# 1_0020-03_FFT2G_-_Top.net
KiCad netlist of a schematic drawn in Altium Designer
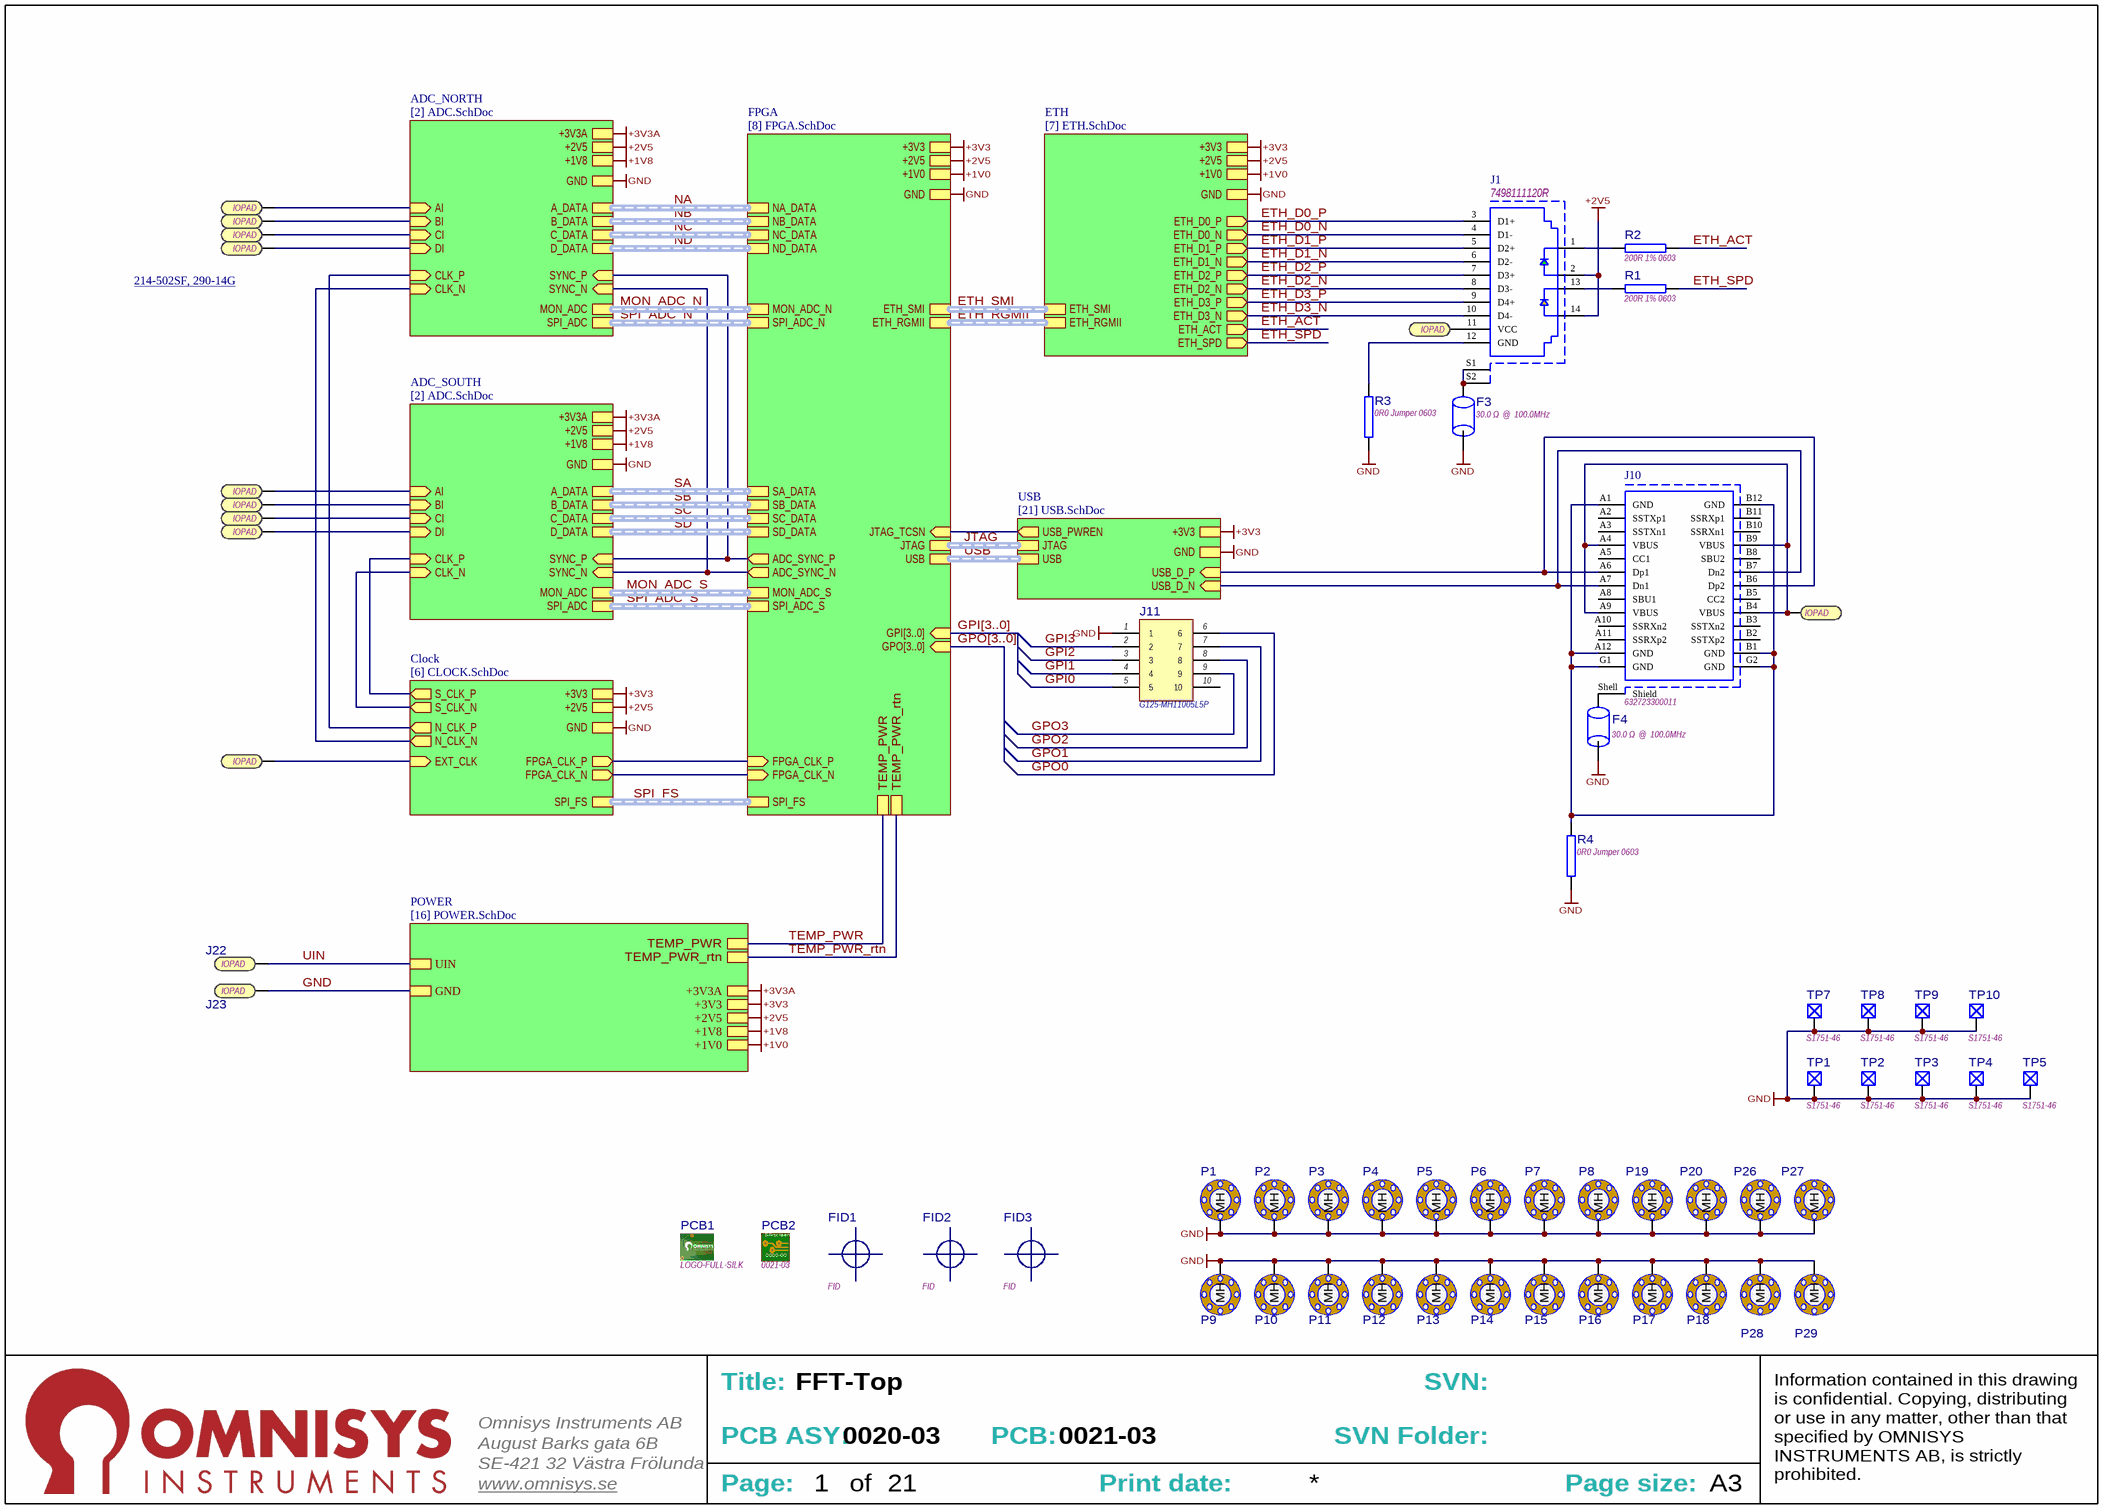
[diagram p0: [1] 0020-03_FFT2G - Top.SchDoc]

(export (version "E")
  (design (tool "Eeschema 10.0.6"))
  (components
    (comp (ref "F3")
      (value "30.0 Ω  @  100.0MHz")
      (footprint "INDC2012X11N")
      (description "Ferrite bead, Würth Elektronik WE-CBF 2012 (0805), 74279206 ,  30.0 Ω  @  100.0MHz")
      (fields (field (name "PARTNUMBER") "74279206"))
      (libsource (lib "Omnisys Vault") (part "BEAD-2PIN"))
    )
    (comp (ref "F4")
      (value "30.0 Ω  @  100.0MHz")
      (footprint "INDC2012X11N")
      (description "Ferrite bead, Würth Elektronik WE-CBF 2012 (0805), 74279206 ,  30.0 Ω  @  100.0MHz")
      (fields (field (name "PARTNUMBER") "74279206"))
      (libsource (lib "Omnisys Vault") (part "BEAD-2PIN"))
    )
    (comp (ref "FID1")
      (value "FID")
      (footprint "FID")
      (description "Pick and place fiducial")
      (libsource (lib "Omnisys Vault") (part "FID"))
    )
    (comp (ref "FID2")
      (value "FID")
      (footprint "FID")
      (description "Pick and place fiducial")
      (libsource (lib "Omnisys Vault") (part "FID"))
    )
    (comp (ref "FID3")
      (value "FID")
      (footprint "FID")
      (description "Pick and place fiducial")
      (libsource (lib "Omnisys Vault") (part "FID"))
    )
    (comp (ref "J1")
      (value "7498111120R")
      (footprint "7498111120R-Footprint-1")
      (description "CONN MAGJACK 1PORT 1000 BASE-T")
      (fields (field (name "PARTNUMBER") "7498111120AR"))
      (libsource (lib "Omnisys Vault") (part "7498111120R"))
    )
    (comp (ref "J2")
      (value "IOPAD")
      (footprint "SMT_IO_PAD_0.5x0.5MM")
      (description "Square IO pad 0.5x0.5mm used for test points and flying leads.")
      (libsource (lib "Omnisys Vault") (part "SMT_IOPAD"))
    )
    (comp (ref "J3")
      (value "IOPAD")
      (footprint "SMT_IO_PAD_0.5x0.5MM")
      (description "Square IO pad 0.5x0.5mm used for test points and flying leads.")
      (libsource (lib "Omnisys Vault") (part "SMT_IOPAD"))
    )
    (comp (ref "J4")
      (value "IOPAD")
      (footprint "SMT_IO_PAD_0.5x0.5MM")
      (description "Square IO pad 0.5x0.5mm used for test points and flying leads.")
      (libsource (lib "Omnisys Vault") (part "SMT_IOPAD"))
    )
    (comp (ref "J5")
      (value "IOPAD")
      (footprint "SMT_IO_PAD_0.5x0.5MM")
      (description "Square IO pad 0.5x0.5mm used for test points and flying leads.")
      (libsource (lib "Omnisys Vault") (part "SMT_IOPAD"))
    )
    (comp (ref "J6")
      (value "IOPAD")
      (footprint "SMT_IO_PAD_0.5x0.5MM")
      (description "Square IO pad 0.5x0.5mm used for test points and flying leads.")
      (libsource (lib "Omnisys Vault") (part "SMT_IOPAD"))
    )
    (comp (ref "J7")
      (value "IOPAD")
      (footprint "SMT_IO_PAD_0.5x0.5MM")
      (description "Square IO pad 0.5x0.5mm used for test points and flying leads.")
      (libsource (lib "Omnisys Vault") (part "SMT_IOPAD"))
    )
    (comp (ref "J8")
      (value "IOPAD")
      (footprint "SMT_IO_PAD_0.5x0.5MM")
      (description "Square IO pad 0.5x0.5mm used for test points and flying leads.")
      (libsource (lib "Omnisys Vault") (part "SMT_IOPAD"))
    )
    (comp (ref "J9")
      (value "IOPAD")
      (footprint "SMT_IO_PAD_0.5x0.5MM")
      (description "Square IO pad 0.5x0.5mm used for test points and flying leads.")
      (libsource (lib "Omnisys Vault") (part "SMT_IOPAD"))
    )
    (comp (ref "J10")
      (value "632723300011")
      (footprint "632723300011")
      (description "USB 3.1 Type C Receptacle WR-COM, Horizontal, SMT / THT")
      (fields (field (name "MANUFACTURER") "Wurth Elektronik") (field (name "PUBLISHER") "WurthElektronik"))
      (libsource (lib "Altium Content Vault") (part "WE-632723X00011"))
    )
    (comp (ref "J11")
      (value "G125-MH11005L5P")
      (footprint "G125-MH11005L5P-Footprint-1")
      (description "CONN HDR 1.25MM R/A PCB 10POS")
      (libsource (lib "Omnisys Vault") (part "CON-2ROW-10PIN-COL"))
    )
    (comp (ref "J15")
      (value "IOPAD")
      (footprint "SMT_IO_PAD_0.5x0.5MM")
      (description "Square IO pad 0.5x0.5mm used for test points and flying leads.")
      (libsource (lib "Omnisys Vault") (part "SMT_IOPAD"))
    )
    (comp (ref "J17")
      (value "IOPAD")
      (footprint "SMT_IO_PAD_2x1MM")
      (description "IO pad used for test points and flying leads.")
      (libsource (lib "Omnisys Vault") (part "SMT_IOPAD"))
    )
    (comp (ref "J18")
      (value "IOPAD")
      (footprint "SMT_IO_PAD_2x1MM")
      (description "IO pad used for test points and flying leads.")
      (libsource (lib "Omnisys Vault") (part "SMT_IOPAD"))
    )
    (comp (ref "J22")
      (value "IOPAD")
      (footprint "SMT_IO_PAD_4x2MM")
      (description "IO pad used for test points and flying leads.")
      (libsource (lib "Omnisys Vault") (part "SMT_IOPAD"))
    )
    (comp (ref "J23")
      (value "IOPAD")
      (footprint "SMT_IO_PAD_4x2MM")
      (description "IO pad used for test points and flying leads.")
      (libsource (lib "Omnisys Vault") (part "SMT_IOPAD"))
    )
    (comp (ref "P1")
      (value "M2.5-6.3mm pad")
      (footprint "MH6.3-2_7MM")
      (description "Mounting hole, M2.5-6.3mm pad")
      (libsource (lib "Omnisys Vault") (part "MH"))
    )
    (comp (ref "P2")
      (value "M2.5-6.3mm pad")
      (footprint "MH6.3-2_7MM")
      (description "Mounting hole, M2.5-6.3mm pad")
      (libsource (lib "Omnisys Vault") (part "MH"))
    )
    (comp (ref "P3")
      (value "M2.5-6.3mm pad")
      (footprint "MH6.3-2_7MM")
      (description "Mounting hole, M2.5-6.3mm pad")
      (libsource (lib "Omnisys Vault") (part "MH"))
    )
    (comp (ref "P4")
      (value "M2.5-6.3mm pad")
      (footprint "MH6.3-2_7MM")
      (description "Mounting hole, M2.5-6.3mm pad")
      (libsource (lib "Omnisys Vault") (part "MH"))
    )
    (comp (ref "P5")
      (value "M2.5-6.3mm pad")
      (footprint "MH6.3-2_7MM")
      (description "Mounting hole, M2.5-6.3mm pad")
      (libsource (lib "Omnisys Vault") (part "MH"))
    )
    (comp (ref "P6")
      (value "M2.5-6.3mm pad")
      (footprint "MH6.3-2_7MM")
      (description "Mounting hole, M2.5-6.3mm pad")
      (libsource (lib "Omnisys Vault") (part "MH"))
    )
    (comp (ref "P7")
      (value "M2.5-6.3mm pad")
      (footprint "MH6.3-2_7MM")
      (description "Mounting hole, M2.5-6.3mm pad")
      (libsource (lib "Omnisys Vault") (part "MH"))
    )
    (comp (ref "P8")
      (value "M2.5-6.3mm pad")
      (footprint "MH6.3-2_7MM")
      (description "Mounting hole, M2.5-6.3mm pad")
      (libsource (lib "Omnisys Vault") (part "MH"))
    )
    (comp (ref "P9")
      (value "M2.5-6.3mm pad")
      (footprint "MH6.3-2_7MM")
      (description "Mounting hole, M2.5-6.3mm pad")
      (libsource (lib "Omnisys Vault") (part "MH"))
    )
    (comp (ref "P10")
      (value "M2.5-6.3mm pad")
      (footprint "MH6.3-2_7MM")
      (description "Mounting hole, M2.5-6.3mm pad")
      (libsource (lib "Omnisys Vault") (part "MH"))
    )
    (comp (ref "P11")
      (value "M2.5-6.3mm pad")
      (footprint "MH6.3-2_7MM")
      (description "Mounting hole, M2.5-6.3mm pad")
      (libsource (lib "Omnisys Vault") (part "MH"))
    )
    (comp (ref "P12")
      (value "M2.5-6.3mm pad")
      (footprint "MH6.3-2_7MM")
      (description "Mounting hole, M2.5-6.3mm pad")
      (libsource (lib "Omnisys Vault") (part "MH"))
    )
    (comp (ref "P13")
      (value "M2.5-6.3mm pad")
      (footprint "MH6.3-2_7MM")
      (description "Mounting hole, M2.5-6.3mm pad")
      (libsource (lib "Omnisys Vault") (part "MH"))
    )
    (comp (ref "P14")
      (value "M2.5-6.3mm pad")
      (footprint "MH6.3-2_7MM")
      (description "Mounting hole, M2.5-6.3mm pad")
      (libsource (lib "Omnisys Vault") (part "MH"))
    )
    (comp (ref "P15")
      (value "M2.5-6.3mm pad")
      (footprint "MH6.3-2_7MM")
      (description "Mounting hole, M2.5-6.3mm pad")
      (libsource (lib "Omnisys Vault") (part "MH"))
    )
    (comp (ref "P16")
      (value "M2.5-6.3mm pad")
      (footprint "MH6.3-2_7MM")
      (description "Mounting hole, M2.5-6.3mm pad")
      (libsource (lib "Omnisys Vault") (part "MH"))
    )
    (comp (ref "P17")
      (value "M2.5-6.3mm pad")
      (footprint "MH6.3-2_7MM")
      (description "Mounting hole, M2.5-6.3mm pad")
      (libsource (lib "Omnisys Vault") (part "MH"))
    )
    (comp (ref "P18")
      (value "M2.5-6.3mm pad")
      (footprint "MH6.3-2_7MM")
      (description "Mounting hole, M2.5-6.3mm pad")
      (libsource (lib "Omnisys Vault") (part "MH"))
    )
    (comp (ref "P19")
      (value "M2.5-6.3mm pad")
      (footprint "MH6.3-2_7MM")
      (description "Mounting hole, M2.5-6.3mm pad")
      (libsource (lib "Omnisys Vault") (part "MH"))
    )
    (comp (ref "P20")
      (value "M2.5-6.3mm pad")
      (footprint "MH6.3-2_7MM")
      (description "Mounting hole, M2.5-6.3mm pad")
      (libsource (lib "Omnisys Vault") (part "MH"))
    )
    (comp (ref "P26")
      (value "M2.5-6.3mm pad")
      (footprint "MH6.3-2_7MM")
      (description "Mounting hole, M2.5-6.3mm pad")
      (libsource (lib "Omnisys Vault") (part "MH"))
    )
    (comp (ref "P27")
      (value "M2.5-6.3mm pad")
      (footprint "MH6.3-2_7MM")
      (description "Mounting hole, M2.5-6.3mm pad")
      (libsource (lib "Omnisys Vault") (part "MH"))
    )
    (comp (ref "P28")
      (value "M2.5-6.3mm pad")
      (footprint "MH6.3-2_7MM")
      (description "Mounting hole, M2.5-6.3mm pad")
      (libsource (lib "Omnisys Vault") (part "MH"))
    )
    (comp (ref "P29")
      (value "M2.5-6.3mm pad")
      (footprint "MH6.3-2_7MM")
      (description "Mounting hole, M2.5-6.3mm pad")
      (libsource (lib "Omnisys Vault") (part "MH"))
    )
    (comp (ref "PCB1")
      (value "LOGO-FULL-SILK")
      (footprint "LOGO-FULL-SILK")
      (description "Full logo in Silkscreen")
      (libsource (lib "Omnisys Vault") (part "CMP-4700-000008-1"))
    )
    (comp (ref "PCB2")
      (value "~")
      (footprint "PCBNo_SILK")
      (description "PCB part number, silkscreen layer")
      (libsource (lib "Omnisys Vault") (part "CMP-4700-000000-3"))
    )
    (comp (ref "R1")
      (value "200R 1% 0603")
      (footprint "RESC1608N")
      (description "Thick film Chip Resistor, 0603/1608")
      (fields (field (name "POWER") "100mW") (field (name "TOLERANCE") "1%"))
      (libsource (lib "Omnisys Vault") (part "RES-2PIN"))
    )
    (comp (ref "R2")
      (value "200R 1% 0603")
      (footprint "RESC1608N")
      (description "Thick film Chip Resistor, 0603/1608")
      (fields (field (name "POWER") "100mW") (field (name "TOLERANCE") "1%"))
      (libsource (lib "Omnisys Vault") (part "RES-2PIN"))
    )
    (comp (ref "R3")
      (value "0R0 Jumper 0603")
      (footprint "RESC1608N")
      (description "Thick film Chip Resistor, 0603/1608")
      (fields (field (name "TOLERANCE") "0%") (field (name "POWER") "0W"))
      (libsource (lib "Omnisys Vault") (part "RES-2PIN"))
    )
    (comp (ref "R4")
      (value "0R0 Jumper 0603")
      (footprint "RESC1608N")
      (description "Thick film Chip Resistor, 0603/1608")
      (fields (field (name "TOLERANCE") "0%") (field (name "POWER") "0W"))
      (libsource (lib "Omnisys Vault") (part "RES-2PIN"))
    )
    (comp (ref "TP1")
      (value "S1751-46")
      (footprint "S1751-46")
      (description "SMD Test point clip")
      (libsource (lib "Omnisys Vault") (part "1-PIN_TP"))
    )
    (comp (ref "TP2")
      (value "S1751-46")
      (footprint "S1751-46")
      (description "SMD Test point clip")
      (libsource (lib "Omnisys Vault") (part "1-PIN_TP"))
    )
    (comp (ref "TP3")
      (value "S1751-46")
      (footprint "S1751-46")
      (description "SMD Test point clip")
      (libsource (lib "Omnisys Vault") (part "1-PIN_TP"))
    )
    (comp (ref "TP4")
      (value "S1751-46")
      (footprint "S1751-46")
      (description "SMD Test point clip")
      (libsource (lib "Omnisys Vault") (part "1-PIN_TP"))
    )
    (comp (ref "TP5")
      (value "S1751-46")
      (footprint "S1751-46")
      (description "SMD Test point clip")
      (libsource (lib "Omnisys Vault") (part "1-PIN_TP"))
    )
    (comp (ref "TP7")
      (value "S1751-46")
      (footprint "S1751-46")
      (description "SMD Test point clip")
      (libsource (lib "Omnisys Vault") (part "1-PIN_TP"))
    )
    (comp (ref "TP8")
      (value "S1751-46")
      (footprint "S1751-46")
      (description "SMD Test point clip")
      (libsource (lib "Omnisys Vault") (part "1-PIN_TP"))
    )
    (comp (ref "TP9")
      (value "S1751-46")
      (footprint "S1751-46")
      (description "SMD Test point clip")
      (libsource (lib "Omnisys Vault") (part "1-PIN_TP"))
    )
    (comp (ref "TP10")
      (value "S1751-46")
      (footprint "S1751-46")
      (description "SMD Test point clip")
      (libsource (lib "Omnisys Vault") (part "1-PIN_TP"))
    )
  )
  (nets
    (net (code "20") (name "+2V5") (class "Default")
      (node (ref "J1") (pin "14") (pinfunction "14_14") (pintype "passive"))
      (node (ref "J1") (pin "2") (pinfunction "2_2") (pintype "passive"))
    )
    (net (code "25") (name "/AI") (class "Default")
      (node (ref "J6") (pin "1") (pinfunction "1_1") (pintype "passive"))
    )
    (net (code "26") (name "/AI_1") (class "Default")
      (node (ref "J2") (pin "1") (pinfunction "1_1") (pintype "passive"))
    )
    (net (code "27") (name "/BI") (class "Default")
      (node (ref "J7") (pin "1") (pinfunction "1_1") (pintype "passive"))
    )
    (net (code "28") (name "/BI_1") (class "Default")
      (node (ref "J3") (pin "1") (pinfunction "1_1") (pintype "passive"))
    )
    (net (code "29") (name "/CI") (class "Default")
      (node (ref "J8") (pin "1") (pinfunction "1_1") (pintype "passive"))
    )
    (net (code "30") (name "/CI_1") (class "Default")
      (node (ref "J4") (pin "1") (pinfunction "1_1") (pintype "passive"))
    )
    (net (code "31") (name "/DI") (class "Default")
      (node (ref "J9") (pin "1") (pinfunction "1_1") (pintype "passive"))
    )
    (net (code "32") (name "/DI_1") (class "Default")
      (node (ref "J5") (pin "1") (pinfunction "1_1") (pintype "passive"))
    )
    (net (code "33") (name "/ETH_ACT") (class "Default")
      (node (ref "R2") (pin "2") (pinfunction "2_2") (pintype "passive"))
    )
    (net (code "34") (name "/ETH_D0_N") (class "Default")
      (node (ref "J1") (pin "4") (pinfunction "D1-_4") (pintype "passive"))
    )
    (net (code "35") (name "/ETH_D0_P") (class "Default")
      (node (ref "J1") (pin "3") (pinfunction "D1+_3") (pintype "passive"))
    )
    (net (code "36") (name "/ETH_D1_N") (class "Default")
      (node (ref "J1") (pin "6") (pinfunction "D2-_6") (pintype "passive"))
    )
    (net (code "37") (name "/ETH_D1_P") (class "Default")
      (node (ref "J1") (pin "5") (pinfunction "D2+_5") (pintype "passive"))
    )
    (net (code "38") (name "/ETH_D2_N") (class "Default")
      (node (ref "J1") (pin "8") (pinfunction "D3-_8") (pintype "passive"))
    )
    (net (code "39") (name "/ETH_D2_P") (class "Default")
      (node (ref "J1") (pin "7") (pinfunction "D3+_7") (pintype "passive"))
    )
    (net (code "40") (name "/ETH_D3_N") (class "Default")
      (node (ref "J1") (pin "10") (pinfunction "D4-_10") (pintype "passive"))
    )
    (net (code "41") (name "/ETH_D3_P") (class "Default")
      (node (ref "J1") (pin "9") (pinfunction "D4+_9") (pintype "passive"))
    )
    (net (code "42") (name "/ETH_SPD") (class "Default")
      (node (ref "R1") (pin "2") (pinfunction "2_2") (pintype "passive"))
    )
    (net (code "43") (name "/EXT_CLK") (class "Default")
      (node (ref "J15") (pin "1") (pinfunction "1_1") (pintype "passive"))
    )
    (net (code "46") (name "/GPI0") (class "Default")
      (node (ref "J11") (pin "5") (pinfunction "5_5") (pintype "passive"))
    )
    (net (code "47") (name "/GPI1") (class "Default")
      (node (ref "J11") (pin "4") (pinfunction "4_4") (pintype "passive"))
    )
    (net (code "48") (name "/GPI2") (class "Default")
      (node (ref "J11") (pin "3") (pinfunction "3_3") (pintype "passive"))
    )
    (net (code "49") (name "/GPI3") (class "Default")
      (node (ref "J11") (pin "2") (pinfunction "2_2") (pintype "passive"))
    )
    (net (code "51") (name "/GPO0") (class "Default")
      (node (ref "J11") (pin "6") (pinfunction "6_6") (pintype "passive"))
    )
    (net (code "52") (name "/GPO1") (class "Default")
      (node (ref "J11") (pin "7") (pinfunction "7_7") (pintype "passive"))
    )
    (net (code "53") (name "/GPO2") (class "Default")
      (node (ref "J11") (pin "8") (pinfunction "8_8") (pintype "passive"))
    )
    (net (code "54") (name "/GPO3") (class "Default")
      (node (ref "J11") (pin "9") (pinfunction "9_9") (pintype "passive"))
    )
    (net (code "62") (name "/UIN") (class "Default")
      (node (ref "J22") (pin "1") (pinfunction "1_1") (pintype "passive"))
    )
    (net (code "63") (name "/USB_D_N") (class "Default")
      (node (ref "J10") (pin "A7") (pinfunction "Dn1_A7") (pintype "passive"))
      (node (ref "J10") (pin "B7") (pinfunction "Dn2_B7") (pintype "passive"))
    )
    (net (code "64") (name "/USB_D_P") (class "Default")
      (node (ref "J10") (pin "A6") (pinfunction "Dp1_A6") (pintype "passive"))
      (node (ref "J10") (pin "B6") (pinfunction "Dp2_B6") (pintype "passive"))
    )
    (net (code "83") (name "GND") (class "Default")
      (node (ref "F3") (pin "1") (pinfunction "1_1") (pintype "passive"))
      (node (ref "F4") (pin "1") (pinfunction "1_1") (pintype "passive"))
      (node (ref "J11") (pin "1") (pinfunction "1_1") (pintype "passive"))
      (node (ref "J23") (pin "1") (pinfunction "1_1") (pintype "passive"))
      (node (ref "P1") (pin "MH") (pinfunction "MH_MH") (pintype "passive"))
      (node (ref "P10") (pin "MH") (pinfunction "MH_MH") (pintype "passive"))
      (node (ref "P11") (pin "MH") (pinfunction "MH_MH") (pintype "passive"))
      (node (ref "P12") (pin "MH") (pinfunction "MH_MH") (pintype "passive"))
      (node (ref "P13") (pin "MH") (pinfunction "MH_MH") (pintype "passive"))
      (node (ref "P14") (pin "MH") (pinfunction "MH_MH") (pintype "passive"))
      (node (ref "P15") (pin "MH") (pinfunction "MH_MH") (pintype "passive"))
      (node (ref "P16") (pin "MH") (pinfunction "MH_MH") (pintype "passive"))
      (node (ref "P17") (pin "MH") (pinfunction "MH_MH") (pintype "passive"))
      (node (ref "P18") (pin "MH") (pinfunction "MH_MH") (pintype "passive"))
      (node (ref "P19") (pin "MH") (pinfunction "MH_MH") (pintype "passive"))
      (node (ref "P2") (pin "MH") (pinfunction "MH_MH") (pintype "passive"))
      (node (ref "P20") (pin "MH") (pinfunction "MH_MH") (pintype "passive"))
      (node (ref "P26") (pin "MH") (pinfunction "MH_MH") (pintype "passive"))
      (node (ref "P27") (pin "MH") (pinfunction "MH_MH") (pintype "passive"))
      (node (ref "P28") (pin "MH") (pinfunction "MH_MH") (pintype "passive"))
      (node (ref "P29") (pin "MH") (pinfunction "MH_MH") (pintype "passive"))
      (node (ref "P3") (pin "MH") (pinfunction "MH_MH") (pintype "passive"))
      (node (ref "P4") (pin "MH") (pinfunction "MH_MH") (pintype "passive"))
      (node (ref "P5") (pin "MH") (pinfunction "MH_MH") (pintype "passive"))
      (node (ref "P6") (pin "MH") (pinfunction "MH_MH") (pintype "passive"))
      (node (ref "P7") (pin "MH") (pinfunction "MH_MH") (pintype "passive"))
      (node (ref "P8") (pin "MH") (pinfunction "MH_MH") (pintype "passive"))
      (node (ref "P9") (pin "MH") (pinfunction "MH_MH") (pintype "passive"))
      (node (ref "R3") (pin "1") (pinfunction "1_1") (pintype "passive"))
      (node (ref "R4") (pin "1") (pinfunction "1_1") (pintype "passive"))
      (node (ref "TP1") (pin "1") (pinfunction "1_1") (pintype "passive"))
      (node (ref "TP10") (pin "1") (pinfunction "1_1") (pintype "passive"))
      (node (ref "TP2") (pin "1") (pinfunction "1_1") (pintype "passive"))
      (node (ref "TP3") (pin "1") (pinfunction "1_1") (pintype "passive"))
      (node (ref "TP4") (pin "1") (pinfunction "1_1") (pintype "passive"))
      (node (ref "TP5") (pin "1") (pinfunction "1_1") (pintype "passive"))
      (node (ref "TP7") (pin "1") (pinfunction "1_1") (pintype "passive"))
      (node (ref "TP8") (pin "1") (pinfunction "1_1") (pintype "passive"))
      (node (ref "TP9") (pin "1") (pinfunction "1_1") (pintype "passive"))
    )
    (net (code "84") (name "Net-(F3-Pad2)") (class "Default")
      (node (ref "F3") (pin "2") (pinfunction "2_2") (pintype "passive"))
      (node (ref "J1") (pin "S1") (pinfunction "Shield_S1") (pintype "passive"))
      (node (ref "J1") (pin "S2") (pinfunction "Shield_S2") (pintype "passive"))
    )
    (net (code "85") (name "Net-(J1-GND)") (class "Default")
      (node (ref "J1") (pin "12") (pinfunction "GND_12") (pintype "passive"))
      (node (ref "R3") (pin "2") (pinfunction "2_2") (pintype "passive"))
    )
    (net (code "86") (name "Net-(J1-Pad1)") (class "Default")
      (node (ref "J1") (pin "1") (pinfunction "1_1") (pintype "passive"))
      (node (ref "R2") (pin "1") (pinfunction "1_1") (pintype "passive"))
    )
    (net (code "87") (name "Net-(J1-Pad13)") (class "Default")
      (node (ref "J1") (pin "13") (pinfunction "13_13") (pintype "passive"))
      (node (ref "R1") (pin "1") (pinfunction "1_1") (pintype "passive"))
    )
    (net (code "88") (name "Net-(J1-VCC)") (class "Default")
      (node (ref "J1") (pin "11") (pinfunction "VCC_11") (pintype "passive"))
      (node (ref "J17") (pin "1") (pinfunction "1_1") (pintype "passive"))
    )
    (net (code "89") (name "Net-(J10-GND-PadA1)") (class "Default")
      (node (ref "J10") (pin "A1") (pinfunction "GND_A1") (pintype "passive"))
      (node (ref "J10") (pin "A12") (pinfunction "GND_A12") (pintype "passive"))
      (node (ref "J10") (pin "B1") (pinfunction "GND_B1") (pintype "passive"))
      (node (ref "J10") (pin "B12") (pinfunction "GND_B12") (pintype "passive"))
      (node (ref "J10") (pin "G1") (pinfunction "GND_G1") (pintype "passive"))
      (node (ref "J10") (pin "G2") (pinfunction "GND_G2") (pintype "passive"))
      (node (ref "R4") (pin "2") (pinfunction "2_2") (pintype "passive"))
    )
    (net (code "90") (name "Net-(J10-Shield)") (class "Default")
      (node (ref "F4") (pin "2") (pinfunction "2_2") (pintype "passive"))
      (node (ref "J10") (pin "Shell") (pinfunction "Shield_Shell") (pintype "passive"))
    )
    (net (code "91") (name "Net-(J10-VBUS-PadA4)") (class "Default")
      (node (ref "J10") (pin "A4") (pinfunction "VBUS_A4") (pintype "passive"))
      (node (ref "J10") (pin "A9") (pinfunction "VBUS_A9") (pintype "passive"))
      (node (ref "J10") (pin "B4") (pinfunction "VBUS_B4") (pintype "passive"))
      (node (ref "J10") (pin "B9") (pinfunction "VBUS_B9") (pintype "passive"))
      (node (ref "J18") (pin "1") (pinfunction "1_1") (pintype "passive"))
    )
    (net (code "92") (name "unconnected-(J10-CC1-PadA5)") (class "Default")
      (node (ref "J10") (pin "A5") (pinfunction "CC1_A5") (pintype "passive"))
    )
    (net (code "93") (name "unconnected-(J10-CC2-PadB5)") (class "Default")
      (node (ref "J10") (pin "B5") (pinfunction "CC2_B5") (pintype "passive"))
    )
    (net (code "94") (name "unconnected-(J10-SBU1-PadA8)") (class "Default")
      (node (ref "J10") (pin "A8") (pinfunction "SBU1_A8") (pintype "passive"))
    )
    (net (code "95") (name "unconnected-(J10-SBU2-PadB8)") (class "Default")
      (node (ref "J10") (pin "B8") (pinfunction "SBU2_B8") (pintype "passive"))
    )
    (net (code "96") (name "unconnected-(J10-SSRXn1-PadB10)") (class "Default")
      (node (ref "J10") (pin "B10") (pinfunction "SSRXn1_B10") (pintype "passive"))
    )
    (net (code "97") (name "unconnected-(J10-SSRXn2-PadA10)") (class "Default")
      (node (ref "J10") (pin "A10") (pinfunction "SSRXn2_A10") (pintype "passive"))
    )
    (net (code "98") (name "unconnected-(J10-SSRXp1-PadB11)") (class "Default")
      (node (ref "J10") (pin "B11") (pinfunction "SSRXp1_B11") (pintype "passive"))
    )
    (net (code "99") (name "unconnected-(J10-SSRXp2-PadA11)") (class "Default")
      (node (ref "J10") (pin "A11") (pinfunction "SSRXp2_A11") (pintype "passive"))
    )
    (net (code "100") (name "unconnected-(J10-SSTXn1-PadA3)") (class "Default")
      (node (ref "J10") (pin "A3") (pinfunction "SSTXn1_A3") (pintype "passive"))
    )
    (net (code "101") (name "unconnected-(J10-SSTXn2-PadB3)") (class "Default")
      (node (ref "J10") (pin "B3") (pinfunction "SSTXn2_B3") (pintype "passive"))
    )
    (net (code "102") (name "unconnected-(J10-SSTXp1-PadA2)") (class "Default")
      (node (ref "J10") (pin "A2") (pinfunction "SSTXp1_A2") (pintype "passive"))
    )
    (net (code "103") (name "unconnected-(J10-SSTXp2-PadB2)") (class "Default")
      (node (ref "J10") (pin "B2") (pinfunction "SSTXp2_B2") (pintype "passive"))
    )
    (net (code "104") (name "unconnected-(J11-Pad10)") (class "Default")
      (node (ref "J11") (pin "10") (pinfunction "10_10") (pintype "passive"))
    )
  )
)
